# 4Z_PCB_2.net
KiCad netlist of a schematic drawn in Altium Designer
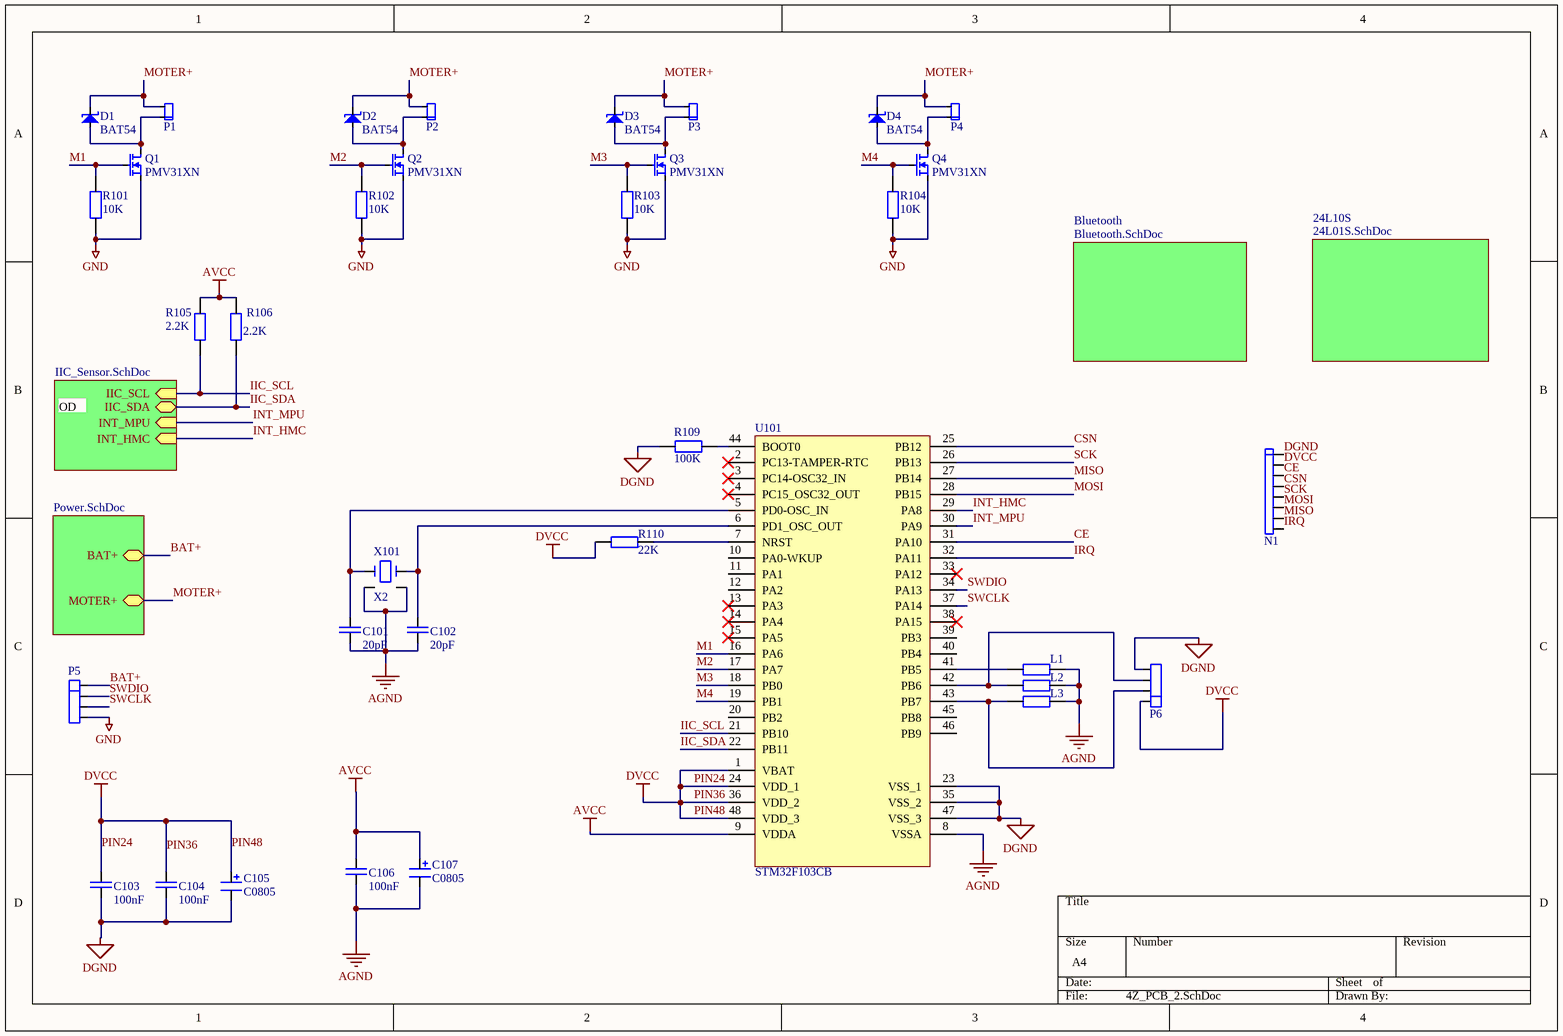
[diagram p0: 4Z_PCB_2.SchDoc]

(export (version "E")
  (design (tool "Eeschema 10.0.6"))
  (components
    (comp (ref "C101") (value "20pF") (footprint "0603") (libsource (lib "Library") (part "C0603")))
    (comp (ref "C102") (value "20pF") (footprint "0603") (libsource (lib "Library") (part "C0603")))
    (comp (ref "C103") (value "100nF") (footprint "0603") (libsource (lib "Library") (part "C0603")))
    (comp (ref "C104") (value "100nF") (footprint "0603") (libsource (lib "Library") (part "C0603")))
    (comp (ref "C105") (value "C0805") (footprint "0805") (libsource (lib "Library") (part "C0805")))
    (comp (ref "C106") (value "100nF") (footprint "0603") (libsource (lib "Library") (part "C0603")))
    (comp (ref "C107") (value "C0805") (footprint "0805") (libsource (lib "Library") (part "C0805")))
    (comp (ref "D1") (value "BAT54") (footprint "BAT54") (libsource (lib "Library") (part "BAT54")))
    (comp (ref "D2") (value "BAT54") (footprint "BAT54") (libsource (lib "Library") (part "BAT54")))
    (comp (ref "D3") (value "BAT54") (footprint "BAT54") (libsource (lib "Library") (part "BAT54")))
    (comp (ref "D4") (value "BAT54") (footprint "BAT54") (libsource (lib "Library") (part "BAT54")))
    (comp (ref "L1") (value "~") (footprint "0603") (libsource (lib "Library") (part "R0603")))
    (comp (ref "L2") (value "~") (footprint "0603") (libsource (lib "Library") (part "R0603")))
    (comp (ref "L3") (value "~") (footprint "0603") (libsource (lib "Library") (part "R0603")))
    (comp (ref "N1") (value "DIP_8") (libsource (lib "Library") (part "DIP_8")))
    (comp (ref "P1") (value "DIP_2") (footprint "DIP_2") (libsource (lib "Library") (part "DIP_2")))
    (comp (ref "P2") (value "DIP_2") (footprint "DIP_2") (libsource (lib "Library") (part "DIP_2")))
    (comp (ref "P3") (value "DIP_2") (footprint "DIP_2") (libsource (lib "Library") (part "DIP_2")))
    (comp (ref "P4") (value "DIP_2") (footprint "DIP_2") (libsource (lib "Library") (part "DIP_2")))
    (comp (ref "P5") (value "DIP_4") (footprint "DIP_4") (libsource (lib "Library") (part "DIP_4")))
    (comp (ref "P6") (value "~") (footprint "DIP_4") (libsource (lib "Library") (part "DIP_4")))
    (comp (ref "Q1")
      (value "PMV31XN")
      (footprint "SOT23-TO236AB")
      (libsource (lib "Library") (part "PMV31XN"))
    )
    (comp (ref "Q2")
      (value "PMV31XN")
      (footprint "SOT23-TO236AB")
      (libsource (lib "Library") (part "PMV31XN"))
    )
    (comp (ref "Q3")
      (value "PMV31XN")
      (footprint "SOT23-TO236AB")
      (libsource (lib "Library") (part "PMV31XN"))
    )
    (comp (ref "Q4")
      (value "PMV31XN")
      (footprint "SOT23-TO236AB")
      (libsource (lib "Library") (part "PMV31XN"))
    )
    (comp (ref "R101") (value "10K") (footprint "0603") (libsource (lib "Library") (part "R0603")))
    (comp (ref "R102") (value "10K") (footprint "0603") (libsource (lib "Library") (part "R0603")))
    (comp (ref "R103") (value "10K") (footprint "0603") (libsource (lib "Library") (part "R0603")))
    (comp (ref "R104") (value "10K") (footprint "0603") (libsource (lib "Library") (part "R0603")))
    (comp (ref "R105") (value "2.2K") (footprint "0603") (libsource (lib "Library") (part "R0603")))
    (comp (ref "R106") (value "2.2K") (footprint "0603") (libsource (lib "Library") (part "R0603")))
    (comp (ref "R109") (value "100K") (footprint "0603") (libsource (lib "Library") (part "R0603")))
    (comp (ref "R110") (value "22K") (footprint "0603") (libsource (lib "Library") (part "R0603")))
    (comp (ref "U101")
      (value "STM32F103CB")
      (footprint "LQFP48")
      (libsource (lib "Library") (part "STM32F103CB"))
    )
    (comp (ref "X101")
      (value "X2")
      (footprint "3225")
      (description "3225")
      (libsource (lib "Library") (part "X2"))
    )
  )
  (nets
    (net (code "1") (name "/BAT+") (class "Default")
      (node (ref "P5") (pin "1") (pinfunction "1_1") (pintype "passive"))
    )
    (net (code "2") (name "/CE") (class "Default")
      (node (ref "N1") (pin "3") (pintype "passive"))
      (node (ref "U101") (pin "31") (pinfunction "PA10_31") (pintype "passive"))
    )
    (net (code "3") (name "/CSN") (class "Default")
      (node (ref "N1") (pin "4") (pintype "passive"))
      (node (ref "U101") (pin "25") (pinfunction "PB12_25") (pintype "passive"))
    )
    (net (code "4") (name "/IIC_SCL") (class "Default")
      (node (ref "R105") (pin "2") (pinfunction "2_2") (pintype "passive"))
      (node (ref "U101") (pin "21") (pinfunction "PB10_21") (pintype "passive"))
    )
    (net (code "5") (name "/IIC_SDA") (class "Default")
      (node (ref "R106") (pin "2") (pinfunction "2_2") (pintype "passive"))
      (node (ref "U101") (pin "22") (pinfunction "PB11_22") (pintype "passive"))
    )
    (net (code "6") (name "/INT_HMC") (class "Default")
      (node (ref "U101") (pin "29") (pinfunction "PA8_29") (pintype "passive"))
    )
    (net (code "7") (name "/INT_MPU") (class "Default")
      (node (ref "U101") (pin "30") (pinfunction "PA9_30") (pintype "passive"))
    )
    (net (code "8") (name "/IRQ") (class "Default")
      (node (ref "N1") (pin "8") (pintype "passive"))
      (node (ref "U101") (pin "32") (pinfunction "PA11_32") (pintype "passive"))
    )
    (net (code "9") (name "/M1") (class "Default")
      (node (ref "Q1") (pin "1") (pinfunction "1_1") (pintype "passive"))
      (node (ref "R101") (pin "1") (pinfunction "1_1") (pintype "passive"))
      (node (ref "U101") (pin "16") (pinfunction "PA6_16") (pintype "passive"))
    )
    (net (code "10") (name "/M2") (class "Default")
      (node (ref "Q2") (pin "1") (pinfunction "1_1") (pintype "passive"))
      (node (ref "R102") (pin "1") (pinfunction "1_1") (pintype "passive"))
      (node (ref "U101") (pin "17") (pinfunction "PA7_17") (pintype "passive"))
    )
    (net (code "11") (name "/M3") (class "Default")
      (node (ref "Q3") (pin "1") (pinfunction "1_1") (pintype "passive"))
      (node (ref "R103") (pin "1") (pinfunction "1_1") (pintype "passive"))
      (node (ref "U101") (pin "18") (pinfunction "PB0_18") (pintype "passive"))
    )
    (net (code "12") (name "/M4") (class "Default")
      (node (ref "Q4") (pin "1") (pinfunction "1_1") (pintype "passive"))
      (node (ref "R104") (pin "1") (pinfunction "1_1") (pintype "passive"))
      (node (ref "U101") (pin "19") (pinfunction "PB1_19") (pintype "passive"))
    )
    (net (code "13") (name "/MISO") (class "Default")
      (node (ref "N1") (pin "7") (pintype "passive"))
      (node (ref "U101") (pin "27") (pinfunction "PB14_27") (pintype "passive"))
    )
    (net (code "14") (name "/MOSI") (class "Default")
      (node (ref "N1") (pin "6") (pintype "passive"))
      (node (ref "U101") (pin "28") (pinfunction "PB15_28") (pintype "passive"))
    )
    (net (code "15") (name "/MOTER+") (class "Default")
      (node (ref "D1") (pin "3") (pinfunction "3_3") (pintype "passive"))
      (node (ref "D2") (pin "3") (pinfunction "3_3") (pintype "passive"))
      (node (ref "D3") (pin "3") (pinfunction "3_3") (pintype "passive"))
      (node (ref "D4") (pin "3") (pinfunction "3_3") (pintype "passive"))
      (node (ref "P1") (pin "2") (pinfunction "2_2") (pintype "passive"))
      (node (ref "P2") (pin "2") (pinfunction "2_2") (pintype "passive"))
      (node (ref "P3") (pin "2") (pinfunction "2_2") (pintype "passive"))
      (node (ref "P4") (pin "2") (pinfunction "2_2") (pintype "passive"))
    )
    (net (code "16") (name "/SCK") (class "Default")
      (node (ref "N1") (pin "5") (pintype "passive"))
      (node (ref "U101") (pin "26") (pinfunction "PB13_26") (pintype "passive"))
    )
    (net (code "17") (name "/SWCLK") (class "Default")
      (node (ref "P5") (pin "3") (pinfunction "3_3") (pintype "passive"))
      (node (ref "U101") (pin "37") (pinfunction "PA14_37") (pintype "passive"))
    )
    (net (code "18") (name "/SWDIO") (class "Default")
      (node (ref "P5") (pin "2") (pinfunction "2_2") (pintype "passive"))
      (node (ref "U101") (pin "34") (pinfunction "PA13_34") (pintype "passive"))
    )
    (net (code "19") (name "AGND") (class "Default")
      (node (ref "C101") (pin "1") (pinfunction "1_1") (pintype "passive"))
      (node (ref "C102") (pin "1") (pinfunction "1_1") (pintype "passive"))
      (node (ref "C106") (pin "1") (pinfunction "1_1") (pintype "passive"))
      (node (ref "C107") (pin "2") (pinfunction "2_2") (pintype "passive"))
      (node (ref "L1") (pin "1") (pinfunction "1_1") (pintype "passive"))
      (node (ref "L2") (pin "1") (pinfunction "1_1") (pintype "passive"))
      (node (ref "L3") (pin "1") (pinfunction "1_1") (pintype "passive"))
      (node (ref "U101") (pin "8") (pinfunction "VSSA_8") (pintype "passive"))
      (node (ref "X101") (pin "2") (pinfunction "2_2") (pintype "passive"))
      (node (ref "X101") (pin "4") (pinfunction "4_4") (pintype "passive"))
    )
    (net (code "20") (name "AVCC") (class "Default")
      (node (ref "C106") (pin "2") (pinfunction "2_2") (pintype "passive"))
      (node (ref "C107") (pin "1") (pinfunction "1_1") (pintype "passive"))
      (node (ref "R105") (pin "1") (pinfunction "1_1") (pintype "passive"))
      (node (ref "R106") (pin "1") (pinfunction "1_1") (pintype "passive"))
      (node (ref "U101") (pin "9") (pinfunction "VDDA_9") (pintype "passive"))
    )
    (net (code "21") (name "DGND") (class "Default")
      (node (ref "C103") (pin "1") (pinfunction "1_1") (pintype "passive"))
      (node (ref "C104") (pin "1") (pinfunction "1_1") (pintype "passive"))
      (node (ref "C105") (pin "2") (pinfunction "2_2") (pintype "passive"))
      (node (ref "N1") (pin "1") (pintype "passive"))
      (node (ref "P6") (pin "4") (pinfunction "4_4") (pintype "passive"))
      (node (ref "R109") (pin "2") (pinfunction "2_2") (pintype "passive"))
      (node (ref "U101") (pin "23") (pinfunction "VSS_1_23") (pintype "passive"))
      (node (ref "U101") (pin "35") (pinfunction "VSS_2_35") (pintype "passive"))
      (node (ref "U101") (pin "47") (pinfunction "VSS_3_47") (pintype "passive"))
    )
    (net (code "22") (name "DVCC") (class "Default")
      (node (ref "C103") (pin "2") (pinfunction "2_2") (pintype "passive"))
      (node (ref "C104") (pin "2") (pinfunction "2_2") (pintype "passive"))
      (node (ref "C105") (pin "1") (pinfunction "1_1") (pintype "passive"))
      (node (ref "N1") (pin "2") (pintype "passive"))
      (node (ref "P6") (pin "1") (pinfunction "1_1") (pintype "passive"))
      (node (ref "R110") (pin "2") (pinfunction "2_2") (pintype "passive"))
      (node (ref "U101") (pin "1") (pinfunction "VBAT_1") (pintype "passive"))
      (node (ref "U101") (pin "24") (pinfunction "VDD_1_24") (pintype "passive"))
      (node (ref "U101") (pin "36") (pinfunction "VDD_2_36") (pintype "passive"))
      (node (ref "U101") (pin "48") (pinfunction "VDD_3_48") (pintype "passive"))
    )
    (net (code "23") (name "GND") (class "Default")
      (node (ref "P5") (pin "4") (pinfunction "4_4") (pintype "passive"))
      (node (ref "Q1") (pin "2") (pinfunction "2_2") (pintype "passive"))
      (node (ref "Q2") (pin "2") (pinfunction "2_2") (pintype "passive"))
      (node (ref "Q3") (pin "2") (pinfunction "2_2") (pintype "passive"))
      (node (ref "Q4") (pin "2") (pinfunction "2_2") (pintype "passive"))
      (node (ref "R101") (pin "2") (pinfunction "2_2") (pintype "passive"))
      (node (ref "R102") (pin "2") (pinfunction "2_2") (pintype "passive"))
      (node (ref "R103") (pin "2") (pinfunction "2_2") (pintype "passive"))
      (node (ref "R104") (pin "2") (pinfunction "2_2") (pintype "passive"))
    )
    (net (code "24") (name "Net-(D1-Pad1)") (class "Default")
      (node (ref "D1") (pin "1") (pinfunction "1_1") (pintype "passive"))
      (node (ref "P1") (pin "1") (pinfunction "1_1") (pintype "passive"))
      (node (ref "Q1") (pin "3") (pinfunction "3_3") (pintype "passive"))
    )
    (net (code "25") (name "Net-(D2-Pad1)") (class "Default")
      (node (ref "D2") (pin "1") (pinfunction "1_1") (pintype "passive"))
      (node (ref "P2") (pin "1") (pinfunction "1_1") (pintype "passive"))
      (node (ref "Q2") (pin "3") (pinfunction "3_3") (pintype "passive"))
    )
    (net (code "26") (name "Net-(D3-Pad1)") (class "Default")
      (node (ref "D3") (pin "1") (pinfunction "1_1") (pintype "passive"))
      (node (ref "P3") (pin "1") (pinfunction "1_1") (pintype "passive"))
      (node (ref "Q3") (pin "3") (pinfunction "3_3") (pintype "passive"))
    )
    (net (code "27") (name "Net-(D4-Pad1)") (class "Default")
      (node (ref "D4") (pin "1") (pinfunction "1_1") (pintype "passive"))
      (node (ref "P4") (pin "1") (pinfunction "1_1") (pintype "passive"))
      (node (ref "Q4") (pin "3") (pinfunction "3_3") (pintype "passive"))
    )
    (net (code "28") (name "Net-(U101-BOOT0)") (class "Default")
      (node (ref "R109") (pin "1") (pinfunction "1_1") (pintype "passive"))
      (node (ref "U101") (pin "44") (pinfunction "BOOT0_44") (pintype "passive"))
    )
    (net (code "29") (name "Net-(U101-NRST)") (class "Default")
      (node (ref "R110") (pin "1") (pinfunction "1_1") (pintype "passive"))
      (node (ref "U101") (pin "7") (pinfunction "NRST_7") (pintype "passive"))
    )
    (net (code "30") (name "Net-(U101-PB5)") (class "Default")
      (node (ref "L1") (pin "2") (pinfunction "2_2") (pintype "passive"))
      (node (ref "U101") (pin "41") (pinfunction "PB5_41") (pintype "passive"))
    )
    (net (code "31") (name "Net-(U101-PB6)") (class "Default")
      (node (ref "L2") (pin "2") (pinfunction "2_2") (pintype "passive"))
      (node (ref "P6") (pin "3") (pinfunction "3_3") (pintype "passive"))
      (node (ref "U101") (pin "42") (pinfunction "PB6_42") (pintype "passive"))
    )
    (net (code "32") (name "Net-(U101-PB7)") (class "Default")
      (node (ref "L3") (pin "2") (pinfunction "2_2") (pintype "passive"))
      (node (ref "P6") (pin "2") (pinfunction "2_2") (pintype "passive"))
      (node (ref "U101") (pin "43") (pinfunction "PB7_43") (pintype "passive"))
    )
    (net (code "33") (name "Net-(U101-PD0-OSC_IN)") (class "Default")
      (node (ref "C101") (pin "2") (pinfunction "2_2") (pintype "passive"))
      (node (ref "U101") (pin "5") (pinfunction "PD0-OSC_IN_5") (pintype "passive"))
      (node (ref "X101") (pin "1") (pintype "passive"))
    )
    (net (code "34") (name "Net-(U101-PD1_OSC_OUT)") (class "Default")
      (node (ref "C102") (pin "2") (pinfunction "2_2") (pintype "passive"))
      (node (ref "U101") (pin "6") (pinfunction "PD1_OSC_OUT_6") (pintype "passive"))
      (node (ref "X101") (pin "3") (pintype "passive"))
    )
    (net (code "35") (name "unconnected-(U101-PA0-WKUP-Pad10)") (class "Default")
      (node (ref "U101") (pin "10") (pinfunction "PA0-WKUP_10") (pintype "passive"))
    )
    (net (code "36") (name "unconnected-(U101-PA1-Pad11)") (class "Default")
      (node (ref "U101") (pin "11") (pinfunction "PA1_11") (pintype "passive"))
    )
    (net (code "37") (name "unconnected-(U101-PA2-Pad12)") (class "Default")
      (node (ref "U101") (pin "12") (pinfunction "PA2_12") (pintype "passive"))
    )
    (net (code "38") (name "unconnected-(U101-PA3-Pad13)") (class "Default")
      (node (ref "U101") (pin "13") (pinfunction "PA3_13") (pintype "passive+no_connect"))
    )
    (net (code "39") (name "unconnected-(U101-PA4-Pad14)") (class "Default")
      (node (ref "U101") (pin "14") (pinfunction "PA4_14") (pintype "passive+no_connect"))
    )
    (net (code "40") (name "unconnected-(U101-PA5-Pad15)") (class "Default")
      (node (ref "U101") (pin "15") (pinfunction "PA5_15") (pintype "passive+no_connect"))
    )
    (net (code "41") (name "unconnected-(U101-PA12-Pad33)") (class "Default")
      (node (ref "U101") (pin "33") (pinfunction "PA12_33") (pintype "passive+no_connect"))
    )
    (net (code "42") (name "unconnected-(U101-PA15-Pad38)") (class "Default")
      (node (ref "U101") (pin "38") (pinfunction "PA15_38") (pintype "passive+no_connect"))
    )
    (net (code "43") (name "unconnected-(U101-PB2-Pad20)") (class "Default")
      (node (ref "U101") (pin "20") (pinfunction "PB2_20") (pintype "passive"))
    )
    (net (code "44") (name "unconnected-(U101-PB3-Pad39)") (class "Default")
      (node (ref "U101") (pin "39") (pinfunction "PB3_39") (pintype "passive"))
    )
    (net (code "45") (name "unconnected-(U101-PB4-Pad40)") (class "Default")
      (node (ref "U101") (pin "40") (pinfunction "PB4_40") (pintype "passive"))
    )
    (net (code "46") (name "unconnected-(U101-PB8-Pad45)") (class "Default")
      (node (ref "U101") (pin "45") (pinfunction "PB8_45") (pintype "passive"))
    )
    (net (code "47") (name "unconnected-(U101-PB9-Pad46)") (class "Default")
      (node (ref "U101") (pin "46") (pinfunction "PB9_46") (pintype "passive"))
    )
    (net (code "48") (name "unconnected-(U101-PC13-TAMPER-RTC-Pad2)") (class "Default")
      (node (ref "U101") (pin "2") (pinfunction "PC13-TAMPER-RTC_2") (pintype "passive+no_connect"))
    )
    (net (code "49") (name "unconnected-(U101-PC14-OSC32_IN-Pad3)") (class "Default")
      (node (ref "U101") (pin "3") (pinfunction "PC14-OSC32_IN_3") (pintype "passive+no_connect"))
    )
    (net (code "50") (name "unconnected-(U101-PC15_OSC32_OUT-Pad4)") (class "Default")
      (node (ref "U101") (pin "4") (pinfunction "PC15_OSC32_OUT_4") (pintype "passive+no_connect"))
    )
  )
)
